# C64_ITFC_X.net
KiCad netlist of a schematic drawn in Altium Designer
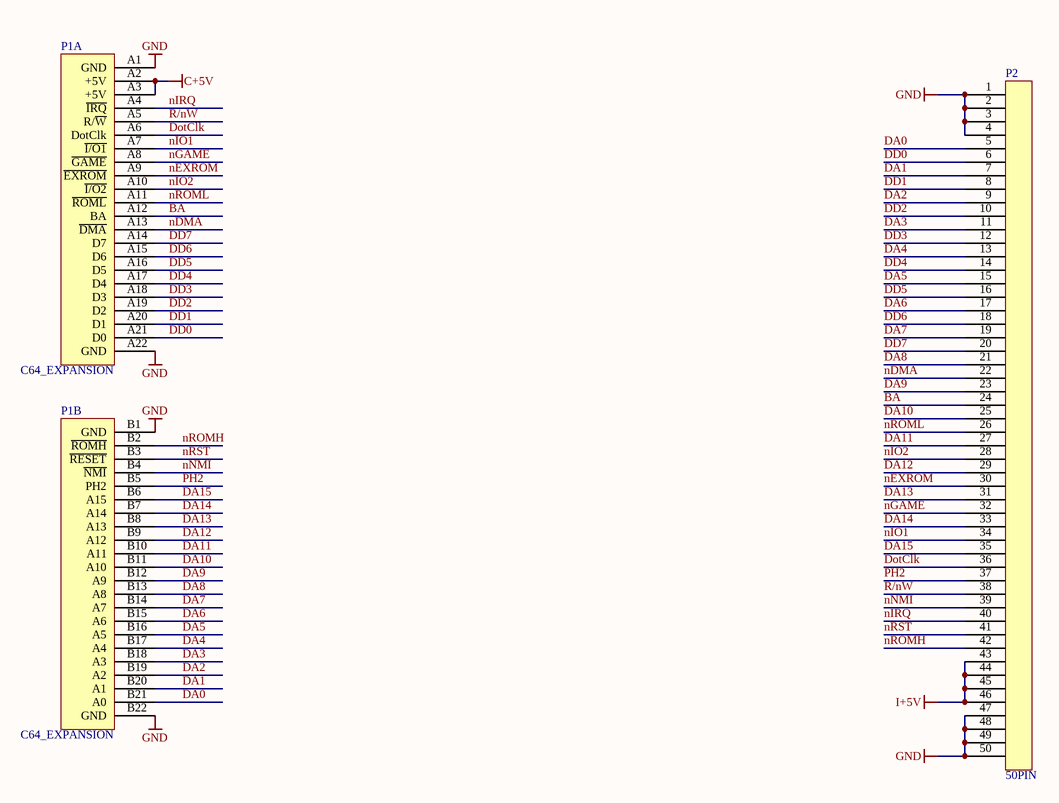
[diagram p0: C64_ITFC_X .SchDoc]

(export (version "E")
  (design (tool "Eeschema 10.0.6"))
  (components
    (comp (ref "P1")
      (value "C64_EXPANSION")
      (footprint "C64_EXPANSION")
      (description "C64 Expansion Connector")
      (libsource (lib "*") (part "C64_EXPANSION"))
    )
    (comp (ref "P2") (value "50PIN") (footprint "IDC50_40") (libsource (lib "*") (part "50PIN")))
  )
  (nets
    (net (code "1") (name "/BA") (class "Default")
      (node (ref "P1") (pin "A12") (pinfunction "BA_A12") (pintype "passive"))
      (node (ref "P2") (pin "24") (pintype "passive"))
    )
    (net (code "2") (name "/DA0") (class "Default")
      (node (ref "P1") (pin "B21") (pinfunction "A0_B21") (pintype "passive"))
      (node (ref "P2") (pin "5") (pintype "passive"))
    )
    (net (code "3") (name "/DA1") (class "Default")
      (node (ref "P1") (pin "B20") (pinfunction "A1_B20") (pintype "passive"))
      (node (ref "P2") (pin "7") (pintype "passive"))
    )
    (net (code "4") (name "/DA2") (class "Default")
      (node (ref "P1") (pin "B19") (pinfunction "A2_B19") (pintype "passive"))
      (node (ref "P2") (pin "9") (pintype "passive"))
    )
    (net (code "5") (name "/DA3") (class "Default")
      (node (ref "P1") (pin "B18") (pinfunction "A3_B18") (pintype "passive"))
      (node (ref "P2") (pin "11") (pintype "passive"))
    )
    (net (code "6") (name "/DA4") (class "Default")
      (node (ref "P1") (pin "B17") (pinfunction "A4_B17") (pintype "passive"))
      (node (ref "P2") (pin "13") (pintype "passive"))
    )
    (net (code "7") (name "/DA5") (class "Default")
      (node (ref "P1") (pin "B16") (pinfunction "A5_B16") (pintype "passive"))
      (node (ref "P2") (pin "15") (pintype "passive"))
    )
    (net (code "8") (name "/DA6") (class "Default")
      (node (ref "P1") (pin "B15") (pinfunction "A6_B15") (pintype "passive"))
      (node (ref "P2") (pin "17") (pintype "passive"))
    )
    (net (code "9") (name "/DA7") (class "Default")
      (node (ref "P1") (pin "B14") (pinfunction "A7_B14") (pintype "passive"))
      (node (ref "P2") (pin "19") (pintype "passive"))
    )
    (net (code "10") (name "/DA8") (class "Default")
      (node (ref "P1") (pin "B13") (pinfunction "A8_B13") (pintype "passive"))
      (node (ref "P2") (pin "21") (pintype "passive"))
    )
    (net (code "11") (name "/DA9") (class "Default")
      (node (ref "P1") (pin "B12") (pinfunction "A9_B12") (pintype "passive"))
      (node (ref "P2") (pin "23") (pintype "passive"))
    )
    (net (code "12") (name "/DA10") (class "Default")
      (node (ref "P1") (pin "B11") (pinfunction "A10_B11") (pintype "passive"))
      (node (ref "P2") (pin "25") (pintype "passive"))
    )
    (net (code "13") (name "/DA11") (class "Default")
      (node (ref "P1") (pin "B10") (pinfunction "A11_B10") (pintype "passive"))
      (node (ref "P2") (pin "27") (pintype "passive"))
    )
    (net (code "14") (name "/DA12") (class "Default")
      (node (ref "P1") (pin "B9") (pinfunction "A12_B9") (pintype "passive"))
      (node (ref "P2") (pin "29") (pintype "passive"))
    )
    (net (code "15") (name "/DA13") (class "Default")
      (node (ref "P1") (pin "B8") (pinfunction "A13_B8") (pintype "passive"))
      (node (ref "P2") (pin "31") (pintype "passive"))
    )
    (net (code "16") (name "/DA14") (class "Default")
      (node (ref "P1") (pin "B7") (pinfunction "A14_B7") (pintype "passive"))
      (node (ref "P2") (pin "33") (pintype "passive"))
    )
    (net (code "17") (name "/DA15") (class "Default")
      (node (ref "P1") (pin "B6") (pinfunction "A15_B6") (pintype "passive"))
      (node (ref "P2") (pin "35") (pintype "passive"))
    )
    (net (code "18") (name "/DD0") (class "Default")
      (node (ref "P1") (pin "A21") (pinfunction "D0_A21") (pintype "passive"))
      (node (ref "P2") (pin "6") (pintype "passive"))
    )
    (net (code "19") (name "/DD1") (class "Default")
      (node (ref "P1") (pin "A20") (pinfunction "D1_A20") (pintype "passive"))
      (node (ref "P2") (pin "8") (pintype "passive"))
    )
    (net (code "20") (name "/DD2") (class "Default")
      (node (ref "P1") (pin "A19") (pinfunction "D2_A19") (pintype "passive"))
      (node (ref "P2") (pin "10") (pintype "passive"))
    )
    (net (code "21") (name "/DD3") (class "Default")
      (node (ref "P1") (pin "A18") (pinfunction "D3_A18") (pintype "passive"))
      (node (ref "P2") (pin "12") (pintype "passive"))
    )
    (net (code "22") (name "/DD4") (class "Default")
      (node (ref "P1") (pin "A17") (pinfunction "D4_A17") (pintype "passive"))
      (node (ref "P2") (pin "14") (pintype "passive"))
    )
    (net (code "23") (name "/DD5") (class "Default")
      (node (ref "P1") (pin "A16") (pinfunction "D5_A16") (pintype "passive"))
      (node (ref "P2") (pin "16") (pintype "passive"))
    )
    (net (code "24") (name "/DD6") (class "Default")
      (node (ref "P1") (pin "A15") (pinfunction "D6_A15") (pintype "passive"))
      (node (ref "P2") (pin "18") (pintype "passive"))
    )
    (net (code "25") (name "/DD7") (class "Default")
      (node (ref "P1") (pin "A14") (pinfunction "D7_A14") (pintype "passive"))
      (node (ref "P2") (pin "20") (pintype "passive"))
    )
    (net (code "26") (name "/DotClk") (class "Default")
      (node (ref "P1") (pin "A6") (pinfunction "DotClk_A6") (pintype "passive"))
      (node (ref "P2") (pin "36") (pintype "passive"))
    )
    (net (code "27") (name "/PH2") (class "Default")
      (node (ref "P1") (pin "B5") (pinfunction "PH2_B5") (pintype "passive"))
      (node (ref "P2") (pin "37") (pintype "passive"))
    )
    (net (code "28") (name "/R{slash}nW") (class "Default")
      (node (ref "P1") (pin "A5") (pinfunction "R/~{W}_A5") (pintype "passive"))
      (node (ref "P2") (pin "38") (pintype "passive"))
    )
    (net (code "29") (name "/nDMA") (class "Default")
      (node (ref "P1") (pin "A13") (pinfunction "~{DMA}_A13") (pintype "passive"))
      (node (ref "P2") (pin "22") (pintype "passive"))
    )
    (net (code "30") (name "/nEXROM") (class "Default")
      (node (ref "P1") (pin "A9") (pinfunction "~{EXROM}_A9") (pintype "passive"))
      (node (ref "P2") (pin "30") (pintype "passive"))
    )
    (net (code "31") (name "/nGAME") (class "Default")
      (node (ref "P1") (pin "A8") (pinfunction "~{GAME}_A8") (pintype "passive"))
      (node (ref "P2") (pin "32") (pintype "passive"))
    )
    (net (code "32") (name "/nIO1") (class "Default")
      (node (ref "P1") (pin "A7") (pinfunction "~{I/O1}_A7") (pintype "passive"))
      (node (ref "P2") (pin "34") (pintype "passive"))
    )
    (net (code "33") (name "/nIO2") (class "Default")
      (node (ref "P1") (pin "A10") (pinfunction "~{I/O2}_A10") (pintype "passive"))
      (node (ref "P2") (pin "28") (pintype "passive"))
    )
    (net (code "34") (name "/nIRQ") (class "Default")
      (node (ref "P1") (pin "A4") (pinfunction "~{IRQ}_A4") (pintype "passive"))
      (node (ref "P2") (pin "40") (pintype "passive"))
    )
    (net (code "35") (name "/nNMI") (class "Default")
      (node (ref "P1") (pin "B4") (pinfunction "~{NMI}_B4") (pintype "passive"))
      (node (ref "P2") (pin "39") (pintype "passive"))
    )
    (net (code "36") (name "/nROMH") (class "Default")
      (node (ref "P1") (pin "B2") (pinfunction "~{ROMH}_B2") (pintype "passive"))
      (node (ref "P2") (pin "42") (pintype "passive"))
    )
    (net (code "37") (name "/nROML") (class "Default")
      (node (ref "P1") (pin "A11") (pinfunction "~{ROML}_A11") (pintype "passive"))
      (node (ref "P2") (pin "26") (pintype "passive"))
    )
    (net (code "38") (name "/nRST") (class "Default")
      (node (ref "P1") (pin "B3") (pinfunction "~{RESET}_B3") (pintype "passive"))
      (node (ref "P2") (pin "41") (pintype "passive"))
    )
    (net (code "39") (name "C+5V") (class "Default")
      (node (ref "P1") (pin "A2") (pinfunction "+5V_A2") (pintype "passive"))
      (node (ref "P1") (pin "A3") (pinfunction "+5V_A3") (pintype "passive"))
    )
    (net (code "40") (name "GND") (class "Default")
      (node (ref "P1") (pin "A1") (pinfunction "GND_A1") (pintype "passive"))
      (node (ref "P1") (pin "A22") (pinfunction "GND_A22") (pintype "passive"))
      (node (ref "P1") (pin "B1") (pinfunction "GND_B1") (pintype "passive"))
      (node (ref "P1") (pin "B22") (pinfunction "GND_B22") (pintype "passive"))
      (node (ref "P2") (pin "1") (pintype "passive"))
      (node (ref "P2") (pin "2") (pintype "passive"))
      (node (ref "P2") (pin "3") (pintype "passive"))
      (node (ref "P2") (pin "4") (pintype "passive"))
      (node (ref "P2") (pin "47") (pintype "passive"))
      (node (ref "P2") (pin "48") (pintype "passive"))
      (node (ref "P2") (pin "49") (pintype "passive"))
      (node (ref "P2") (pin "50") (pintype "passive"))
    )
    (net (code "41") (name "I+5V") (class "Default")
      (node (ref "P2") (pin "43") (pintype "passive"))
      (node (ref "P2") (pin "44") (pintype "passive"))
      (node (ref "P2") (pin "45") (pintype "passive"))
      (node (ref "P2") (pin "46") (pintype "passive"))
    )
  )
)
